# ArtixBank14.net
KiCad netlist of a schematic drawn in Altium Designer
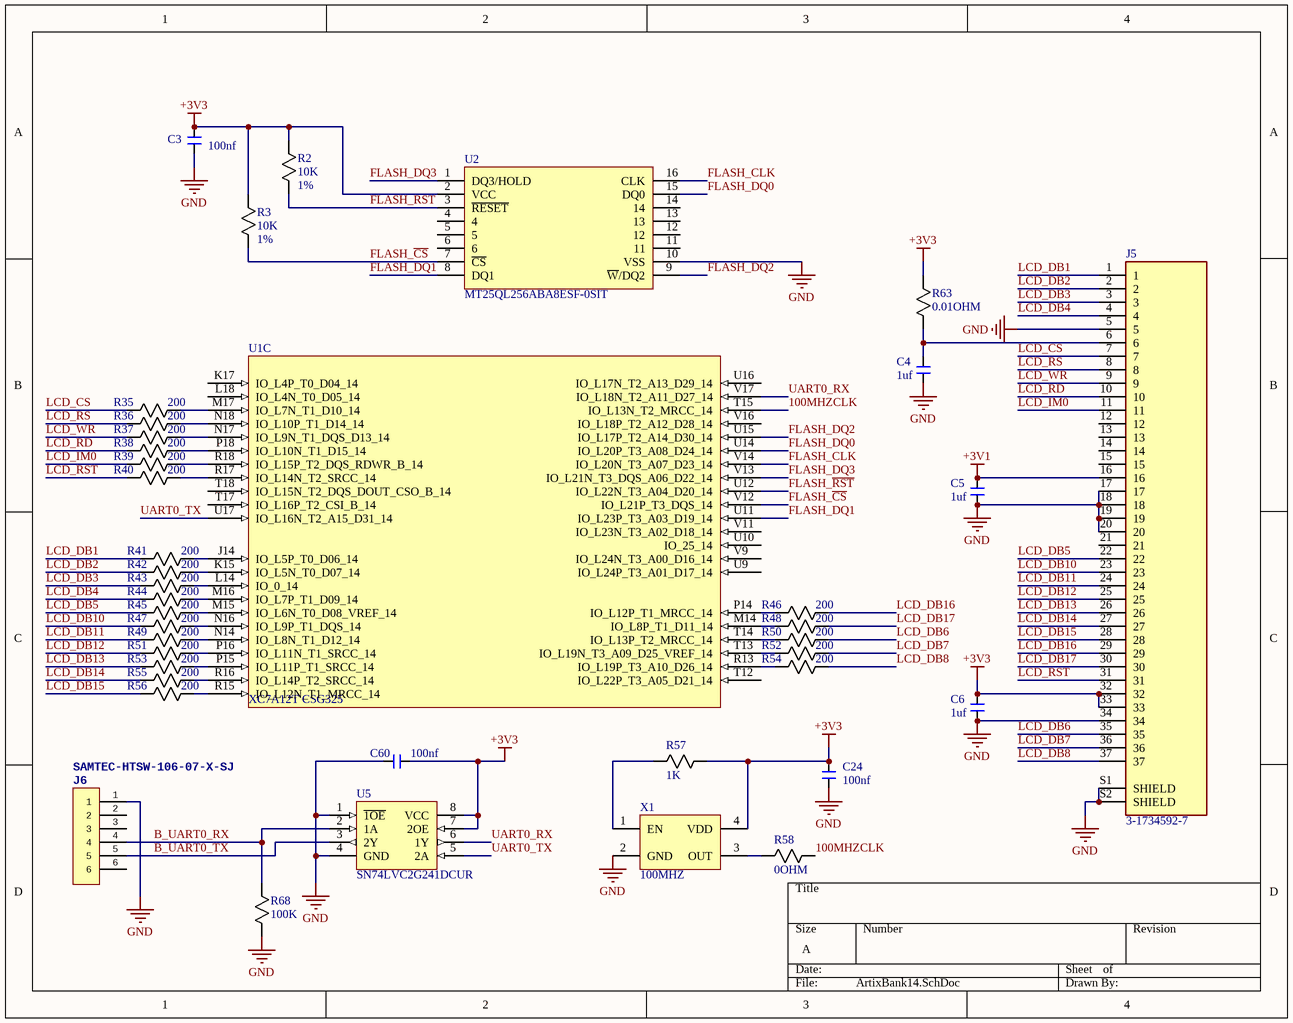
[diagram p0: ArtixBank14.SchDoc]

(export (version "E")
  (design (tool "Eeschema 10.0.6"))
  (components
    (comp (ref "C3")
      (value "100nf")
      (footprint "0402Footprint")
      (description "0402")
      (libsource (lib "Capacitors") (part "100nf_0402"))
    )
    (comp (ref "C4")
      (value "1uf")
      (footprint "0402Footprint")
      (description "0402")
      (libsource (lib "Capacitors") (part "1uf_0402"))
    )
    (comp (ref "C5")
      (value "1uf")
      (footprint "0402Footprint")
      (description "0402")
      (libsource (lib "Capacitors") (part "1uf_0402"))
    )
    (comp (ref "C6")
      (value "1uf")
      (footprint "0402Footprint")
      (description "0402")
      (libsource (lib "Capacitors") (part "1uf_0402"))
    )
    (comp (ref "C24")
      (value "100nf")
      (footprint "0402Footprint")
      (description "0402")
      (libsource (lib "Capacitors") (part "100nf_0402"))
    )
    (comp (ref "C60")
      (value "100nf")
      (footprint "0402Footprint")
      (description "0402")
      (libsource (lib "Capacitors") (part "100nf_0402"))
    )
    (comp (ref "J5")
      (value "3-1734592-7")
      (footprint "TE_3-1734592-7")
      (description "Conn FPC Connector SKT 37 POS 0.5mm Solder RA SMD T/R")
      (fields (field (name "MF") "TE Connectivity"))
      (libsource (lib "3-1734592-7") (part "3-1734592-7"))
    )
    (comp (ref "J6")
      (value "SAMTEC-HTSW-106-07-X-SJ")
      (footprint "SAMTEC-HTSW-106-07-X-S")
      (description "6 pin 2.54mm pitch header")
      (libsource (lib "Connectors") (part "SAMTEC-HTSW-106-07-X-SJ"))
    )
    (comp (ref "R2")
      (value "10K")
      (footprint "RES_CRCW_0402")
      (description "0402")
      (fields (field (name "TOLERANCE") "1%"))
      (libsource (lib "Resistors") (part "10K_0402"))
    )
    (comp (ref "R3")
      (value "10K")
      (footprint "RES_CRCW_0402")
      (description "0402")
      (fields (field (name "TOLERANCE") "1%"))
      (libsource (lib "Resistors") (part "10K_0402"))
    )
    (comp (ref "R35")
      (value "200")
      (footprint "RES_CRCW_0402")
      (description "0402")
      (fields (field (name "TOLERANCE") "1%"))
      (libsource (lib "Resistors") (part "200OHM_0402"))
    )
    (comp (ref "R36")
      (value "200")
      (footprint "RES_CRCW_0402")
      (description "0402")
      (fields (field (name "TOLERANCE") "1%"))
      (libsource (lib "Resistors") (part "200OHM_0402"))
    )
    (comp (ref "R37")
      (value "200")
      (footprint "RES_CRCW_0402")
      (description "0402")
      (fields (field (name "TOLERANCE") "1%"))
      (libsource (lib "Resistors") (part "200OHM_0402"))
    )
    (comp (ref "R38")
      (value "200")
      (footprint "RES_CRCW_0402")
      (description "0402")
      (fields (field (name "TOLERANCE") "1%"))
      (libsource (lib "Resistors") (part "200OHM_0402"))
    )
    (comp (ref "R39")
      (value "200")
      (footprint "RES_CRCW_0402")
      (description "0402")
      (fields (field (name "TOLERANCE") "1%"))
      (libsource (lib "Resistors") (part "200OHM_0402"))
    )
    (comp (ref "R40")
      (value "200")
      (footprint "RES_CRCW_0402")
      (description "0402")
      (fields (field (name "TOLERANCE") "1%"))
      (libsource (lib "Resistors") (part "200OHM_0402"))
    )
    (comp (ref "R41")
      (value "200")
      (footprint "RES_CRCW_0402")
      (description "0402")
      (fields (field (name "TOLERANCE") "1%"))
      (libsource (lib "Resistors") (part "200OHM_0402"))
    )
    (comp (ref "R42")
      (value "200")
      (footprint "RES_CRCW_0402")
      (description "0402")
      (fields (field (name "TOLERANCE") "1%"))
      (libsource (lib "Resistors") (part "200OHM_0402"))
    )
    (comp (ref "R43")
      (value "200")
      (footprint "RES_CRCW_0402")
      (description "0402")
      (fields (field (name "TOLERANCE") "1%"))
      (libsource (lib "Resistors") (part "200OHM_0402"))
    )
    (comp (ref "R44")
      (value "200")
      (footprint "RES_CRCW_0402")
      (description "0402")
      (fields (field (name "TOLERANCE") "1%"))
      (libsource (lib "Resistors") (part "200OHM_0402"))
    )
    (comp (ref "R45")
      (value "200")
      (footprint "RES_CRCW_0402")
      (description "0402")
      (fields (field (name "TOLERANCE") "1%"))
      (libsource (lib "Resistors") (part "200OHM_0402"))
    )
    (comp (ref "R46")
      (value "200")
      (footprint "RES_CRCW_0402")
      (description "0402")
      (fields (field (name "TOLERANCE") "1%"))
      (libsource (lib "Resistors") (part "200OHM_0402"))
    )
    (comp (ref "R47")
      (value "200")
      (footprint "RES_CRCW_0402")
      (description "0402")
      (fields (field (name "TOLERANCE") "1%"))
      (libsource (lib "Resistors") (part "200OHM_0402"))
    )
    (comp (ref "R48")
      (value "200")
      (footprint "RES_CRCW_0402")
      (description "0402")
      (fields (field (name "TOLERANCE") "1%"))
      (libsource (lib "Resistors") (part "200OHM_0402"))
    )
    (comp (ref "R49")
      (value "200")
      (footprint "RES_CRCW_0402")
      (description "0402")
      (fields (field (name "TOLERANCE") "1%"))
      (libsource (lib "Resistors") (part "200OHM_0402"))
    )
    (comp (ref "R50")
      (value "200")
      (footprint "RES_CRCW_0402")
      (description "0402")
      (fields (field (name "TOLERANCE") "1%"))
      (libsource (lib "Resistors") (part "200OHM_0402"))
    )
    (comp (ref "R51")
      (value "200")
      (footprint "RES_CRCW_0402")
      (description "0402")
      (fields (field (name "TOLERANCE") "1%"))
      (libsource (lib "Resistors") (part "200OHM_0402"))
    )
    (comp (ref "R52")
      (value "200")
      (footprint "RES_CRCW_0402")
      (description "0402")
      (fields (field (name "TOLERANCE") "1%"))
      (libsource (lib "Resistors") (part "200OHM_0402"))
    )
    (comp (ref "R53")
      (value "200")
      (footprint "RES_CRCW_0402")
      (description "0402")
      (fields (field (name "TOLERANCE") "1%"))
      (libsource (lib "Resistors") (part "200OHM_0402"))
    )
    (comp (ref "R54")
      (value "200")
      (footprint "RES_CRCW_0402")
      (description "0402")
      (fields (field (name "TOLERANCE") "1%"))
      (libsource (lib "Resistors") (part "200OHM_0402"))
    )
    (comp (ref "R55")
      (value "200")
      (footprint "RES_CRCW_0402")
      (description "0402")
      (fields (field (name "TOLERANCE") "1%"))
      (libsource (lib "Resistors") (part "200OHM_0402"))
    )
    (comp (ref "R56")
      (value "200")
      (footprint "RES_CRCW_0402")
      (description "0402")
      (fields (field (name "TOLERANCE") "1%"))
      (libsource (lib "Resistors") (part "200OHM_0402"))
    )
    (comp (ref "R57")
      (value "1K")
      (footprint "RES_CRCW_0402")
      (description "0402")
      (fields (field (name "TOLERANCE") "1%"))
      (libsource (lib "Resistors") (part "1k_0402"))
    )
    (comp (ref "R58")
      (value "0OHM")
      (footprint "RES_CRCW_0402")
      (description "0402")
      (libsource (lib "Resistors") (part "0OHM_0402"))
    )
    (comp (ref "R63")
      (value "0.01OHM")
      (footprint "RESC1508X06N")
      (description "0603")
      (libsource (lib "Resistors") (part "0.01OHM_0603"))
    )
    (comp (ref "R68")
      (value "100K")
      (footprint "RES_CRCW_0402")
      (description "0402")
      (fields (field (name "TOLERANCE") "1%"))
      (libsource (lib "Resistors") (part "100K_0402"))
    )
    (comp (ref "U1")
      (value "XC7A12T CSG325")
      (footprint "BGA324C80P18X18_1500X1500X150")
      (libsource (lib "XC7A12T_1CPG238I") (part "XC7A12T_1CSG325I"))
    )
    (comp (ref "U2")
      (value "MT25QL256ABA8ESF-0SIT")
      (footprint "SOP127P1030X265-16N")
      (description "256 Mb Flash Micron")
      (libsource (lib "MT25QL256ABA") (part "MT25QL256ABA8ESF-0SIT"))
    )
    (comp (ref "U5")
      (value "SN74LVC2G241DCUR")
      (footprint "SOP50P310X90-8N")
      (description "Buffer, Non-Inverting 2 Element 1 Bit per Element 3-State Output 8-VSSOP")
      (fields (field (name "MF") "Texas Instruments"))
      (libsource (lib "SN74LVC2G241DCUR") (part "SN74LVC2G241DCUR"))
    )
    (comp (ref "X1")
      (value "100MHZ")
      (footprint "SIT8008AI-12-33E-100.000000E")
      (libsource (lib "Oscillators") (part "SIT8008AI-12-33E-100.000000E"))
    )
  )
  (nets
    (net (code "1") (name "+3V1") (class "Default")
      (node (ref "C5") (pin "1") (pinfunction "1_1") (pintype "passive"))
      (node (ref "J5") (pin "16") (pinfunction "16_16") (pintype "passive"))
    )
    (net (code "2") (name "+3V3") (class "Default")
      (node (ref "C24") (pin "1") (pinfunction "1_1") (pintype "passive"))
      (node (ref "C3") (pin "1") (pinfunction "1_1") (pintype "passive"))
      (node (ref "C6") (pin "1") (pinfunction "1_1") (pintype "passive"))
      (node (ref "C60") (pin "1") (pinfunction "1_1") (pintype "passive"))
      (node (ref "J5") (pin "32") (pinfunction "32_32") (pintype "passive"))
      (node (ref "J5") (pin "33") (pinfunction "33_33") (pintype "passive"))
      (node (ref "R2") (pin "1") (pinfunction "1_1") (pintype "passive"))
      (node (ref "R3") (pin "1") (pinfunction "1_1") (pintype "passive"))
      (node (ref "R57") (pin "1") (pinfunction "1_1") (pintype "passive"))
      (node (ref "R63") (pin "1") (pinfunction "1_1") (pintype "passive"))
      (node (ref "U2") (pin "2") (pinfunction "VCC_2") (pintype "passive"))
      (node (ref "U5") (pin "7") (pinfunction "2OE_7") (pintype "input"))
      (node (ref "U5") (pin "8") (pinfunction "VCC_8") (pintype "power_in"))
      (node (ref "X1") (pin "4") (pinfunction "VDD_4") (pintype "passive"))
    )
    (net (code "3") (name "/100MHZCLK") (class "Default")
      (node (ref "R58") (pin "1") (pinfunction "1_1") (pintype "passive"))
      (node (ref "U1") (pin "T15") (pinfunction "IO_L13N_T2_MRCC_14_T15") (pintype "input"))
    )
    (net (code "4") (name "/B_UART0_RX") (class "Default")
      (node (ref "J6") (pin "4") (pinfunction "4_4") (pintype "passive"))
      (node (ref "R68") (pin "1") (pinfunction "1_1") (pintype "passive"))
      (node (ref "U5") (pin "2") (pinfunction "1A_2") (pintype "input"))
    )
    (net (code "5") (name "/B_UART0_TX") (class "Default")
      (node (ref "J6") (pin "5") (pinfunction "5_5") (pintype "passive"))
      (node (ref "U5") (pin "3") (pinfunction "2Y_3") (pintype "output"))
    )
    (net (code "6") (name "/FLASH_CLK") (class "Default")
      (node (ref "U1") (pin "V14") (pinfunction "IO_L20N_T3_A07_D23_14_V14") (pintype "input"))
      (node (ref "U2") (pin "16") (pinfunction "CLK_16") (pintype "passive"))
    )
    (net (code "7") (name "/FLASH_DQ0") (class "Default")
      (node (ref "U1") (pin "U14") (pinfunction "IO_L20P_T3_A08_D24_14_U14") (pintype "input"))
      (node (ref "U2") (pin "15") (pinfunction "DQ0_15") (pintype "passive"))
    )
    (net (code "8") (name "/FLASH_DQ1") (class "Default")
      (node (ref "U1") (pin "U11") (pinfunction "IO_L23P_T3_A03_D19_14_U11") (pintype "input"))
      (node (ref "U2") (pin "8") (pinfunction "DQ1_8") (pintype "passive"))
    )
    (net (code "9") (name "/FLASH_DQ2") (class "Default")
      (node (ref "U1") (pin "U15") (pinfunction "IO_L17P_T2_A14_D30_14_U15") (pintype "input"))
      (node (ref "U2") (pin "9") (pinfunction "~{W}/DQ2_9") (pintype "passive"))
    )
    (net (code "10") (name "/FLASH_DQ3") (class "Default")
      (node (ref "U1") (pin "V13") (pinfunction "IO_L21N_T3_DQS_A06_D22_14_V13") (pintype "input"))
      (node (ref "U2") (pin "1") (pinfunction "DQ3/HOLD_1") (pintype "passive"))
    )
    (net (code "11") (name "/FLASH_~{CS}") (class "Default")
      (node (ref "R3") (pin "2") (pinfunction "2_2") (pintype "passive"))
      (node (ref "U1") (pin "V12") (pinfunction "IO_L21P_T3_DQS_14_V12") (pintype "input"))
      (node (ref "U2") (pin "7") (pinfunction "~{CS}_7") (pintype "passive"))
    )
    (net (code "12") (name "/FLASH_~{RST}") (class "Default")
      (node (ref "R2") (pin "2") (pinfunction "2_2") (pintype "passive"))
      (node (ref "U1") (pin "U12") (pinfunction "IO_L22N_T3_A04_D20_14_U12") (pintype "input"))
      (node (ref "U2") (pin "3") (pinfunction "~{RESET}_3") (pintype "passive"))
    )
    (net (code "13") (name "/LCD_CS") (class "Default")
      (node (ref "J5") (pin "7") (pinfunction "7_7") (pintype "passive"))
      (node (ref "R35") (pin "2") (pinfunction "2_2") (pintype "passive"))
    )
    (net (code "14") (name "/LCD_DB1") (class "Default")
      (node (ref "J5") (pin "1") (pinfunction "1_1") (pintype "passive"))
      (node (ref "R41") (pin "2") (pinfunction "2_2") (pintype "passive"))
    )
    (net (code "15") (name "/LCD_DB2") (class "Default")
      (node (ref "J5") (pin "2") (pinfunction "2_2") (pintype "passive"))
      (node (ref "R42") (pin "2") (pinfunction "2_2") (pintype "passive"))
    )
    (net (code "16") (name "/LCD_DB3") (class "Default")
      (node (ref "J5") (pin "3") (pinfunction "3_3") (pintype "passive"))
      (node (ref "R43") (pin "2") (pinfunction "2_2") (pintype "passive"))
    )
    (net (code "17") (name "/LCD_DB4") (class "Default")
      (node (ref "J5") (pin "4") (pinfunction "4_4") (pintype "passive"))
      (node (ref "R44") (pin "2") (pinfunction "2_2") (pintype "passive"))
    )
    (net (code "18") (name "/LCD_DB5") (class "Default")
      (node (ref "J5") (pin "22") (pinfunction "22_22") (pintype "passive"))
      (node (ref "R45") (pin "2") (pinfunction "2_2") (pintype "passive"))
    )
    (net (code "19") (name "/LCD_DB6") (class "Default")
      (node (ref "J5") (pin "35") (pinfunction "35_35") (pintype "passive"))
      (node (ref "R50") (pin "1") (pinfunction "1_1") (pintype "passive"))
    )
    (net (code "20") (name "/LCD_DB7") (class "Default")
      (node (ref "J5") (pin "36") (pinfunction "36_36") (pintype "passive"))
      (node (ref "R52") (pin "1") (pinfunction "1_1") (pintype "passive"))
    )
    (net (code "21") (name "/LCD_DB8") (class "Default")
      (node (ref "J5") (pin "37") (pinfunction "37_37") (pintype "passive"))
      (node (ref "R54") (pin "1") (pinfunction "1_1") (pintype "passive"))
    )
    (net (code "22") (name "/LCD_DB10") (class "Default")
      (node (ref "J5") (pin "23") (pinfunction "23_23") (pintype "passive"))
      (node (ref "R47") (pin "2") (pinfunction "2_2") (pintype "passive"))
    )
    (net (code "23") (name "/LCD_DB11") (class "Default")
      (node (ref "J5") (pin "24") (pinfunction "24_24") (pintype "passive"))
      (node (ref "R49") (pin "2") (pinfunction "2_2") (pintype "passive"))
    )
    (net (code "24") (name "/LCD_DB12") (class "Default")
      (node (ref "J5") (pin "25") (pinfunction "25_25") (pintype "passive"))
      (node (ref "R51") (pin "2") (pinfunction "2_2") (pintype "passive"))
    )
    (net (code "25") (name "/LCD_DB13") (class "Default")
      (node (ref "J5") (pin "26") (pinfunction "26_26") (pintype "passive"))
      (node (ref "R53") (pin "2") (pinfunction "2_2") (pintype "passive"))
    )
    (net (code "26") (name "/LCD_DB14") (class "Default")
      (node (ref "J5") (pin "27") (pinfunction "27_27") (pintype "passive"))
      (node (ref "R55") (pin "2") (pinfunction "2_2") (pintype "passive"))
    )
    (net (code "27") (name "/LCD_DB15") (class "Default")
      (node (ref "J5") (pin "28") (pinfunction "28_28") (pintype "passive"))
      (node (ref "R56") (pin "2") (pinfunction "2_2") (pintype "passive"))
    )
    (net (code "28") (name "/LCD_DB16") (class "Default")
      (node (ref "J5") (pin "29") (pinfunction "29_29") (pintype "passive"))
      (node (ref "R46") (pin "1") (pinfunction "1_1") (pintype "passive"))
    )
    (net (code "29") (name "/LCD_DB17") (class "Default")
      (node (ref "J5") (pin "30") (pinfunction "30_30") (pintype "passive"))
      (node (ref "R48") (pin "1") (pinfunction "1_1") (pintype "passive"))
    )
    (net (code "30") (name "/LCD_IM0") (class "Default")
      (node (ref "J5") (pin "11") (pinfunction "11_11") (pintype "passive"))
      (node (ref "R39") (pin "2") (pinfunction "2_2") (pintype "passive"))
    )
    (net (code "31") (name "/LCD_RD") (class "Default")
      (node (ref "J5") (pin "10") (pinfunction "10_10") (pintype "passive"))
      (node (ref "R38") (pin "2") (pinfunction "2_2") (pintype "passive"))
    )
    (net (code "32") (name "/LCD_RS") (class "Default")
      (node (ref "J5") (pin "8") (pinfunction "8_8") (pintype "passive"))
      (node (ref "R36") (pin "2") (pinfunction "2_2") (pintype "passive"))
    )
    (net (code "33") (name "/LCD_RST") (class "Default")
      (node (ref "J5") (pin "31") (pinfunction "31_31") (pintype "passive"))
      (node (ref "R40") (pin "2") (pinfunction "2_2") (pintype "passive"))
    )
    (net (code "34") (name "/LCD_WR") (class "Default")
      (node (ref "J5") (pin "9") (pinfunction "9_9") (pintype "passive"))
      (node (ref "R37") (pin "2") (pinfunction "2_2") (pintype "passive"))
    )
    (net (code "35") (name "/UART0_RX") (class "Default")
      (node (ref "U1") (pin "V17") (pinfunction "IO_L18N_T2_A11_D27_14_V17") (pintype "input"))
      (node (ref "U5") (pin "6") (pinfunction "1Y_6") (pintype "output"))
    )
    (net (code "36") (name "/UART0_TX") (class "Default")
      (node (ref "U1") (pin "U17") (pinfunction "IO_L16N_T2_A15_D31_14_U17") (pintype "input"))
      (node (ref "U5") (pin "5") (pinfunction "2A_5") (pintype "input"))
    )
    (net (code "37") (name "GND") (class "Default")
      (node (ref "C24") (pin "2") (pinfunction "2_2") (pintype "passive"))
      (node (ref "C3") (pin "2") (pinfunction "2_2") (pintype "passive"))
      (node (ref "C4") (pin "2") (pinfunction "2_2") (pintype "passive"))
      (node (ref "C5") (pin "2") (pinfunction "2_2") (pintype "passive"))
      (node (ref "C6") (pin "2") (pinfunction "2_2") (pintype "passive"))
      (node (ref "C60") (pin "2") (pinfunction "2_2") (pintype "passive"))
      (node (ref "J5") (pin "17") (pinfunction "17_17") (pintype "passive"))
      (node (ref "J5") (pin "18") (pinfunction "18_18") (pintype "passive"))
      (node (ref "J5") (pin "19") (pinfunction "19_19") (pintype "passive"))
      (node (ref "J5") (pin "20") (pinfunction "20_20") (pintype "passive"))
      (node (ref "J5") (pin "34") (pinfunction "34_34") (pintype "passive"))
      (node (ref "J5") (pin "5") (pinfunction "5_5") (pintype "passive"))
      (node (ref "J5") (pin "S1") (pinfunction "SHIELD_S1") (pintype "passive"))
      (node (ref "J5") (pin "S2") (pinfunction "SHIELD_S2") (pintype "passive"))
      (node (ref "J6") (pin "1") (pinfunction "1_1") (pintype "passive"))
      (node (ref "R68") (pin "2") (pinfunction "2_2") (pintype "passive"))
      (node (ref "U2") (pin "10") (pinfunction "VSS_10") (pintype "passive"))
      (node (ref "U5") (pin "1") (pinfunction "~{1OE}_1") (pintype "input"))
      (node (ref "U5") (pin "4") (pinfunction "GND_4") (pintype "passive"))
      (node (ref "X1") (pin "2") (pinfunction "GND_2") (pintype "passive"))
    )
    (net (code "38") (name "Net-(C4-Pad1)") (class "Default")
      (node (ref "C4") (pin "1") (pinfunction "1_1") (pintype "passive"))
      (node (ref "J5") (pin "6") (pinfunction "6_6") (pintype "passive"))
      (node (ref "R63") (pin "2") (pinfunction "2_2") (pintype "passive"))
    )
    (net (code "39") (name "Net-(U1C-IO_0_14)") (class "Default")
      (node (ref "R43") (pin "1") (pinfunction "1_1") (pintype "passive"))
      (node (ref "U1") (pin "L14") (pinfunction "IO_0_14_L14") (pintype "input"))
    )
    (net (code "40") (name "Net-(U1C-IO_L5N_T0_D07_14)") (class "Default")
      (node (ref "R42") (pin "1") (pinfunction "1_1") (pintype "passive"))
      (node (ref "U1") (pin "K15") (pinfunction "IO_L5N_T0_D07_14_K15") (pintype "input"))
    )
    (net (code "41") (name "Net-(U1C-IO_L5P_T0_D06_14)") (class "Default")
      (node (ref "R41") (pin "1") (pinfunction "1_1") (pintype "passive"))
      (node (ref "U1") (pin "J14") (pinfunction "IO_L5P_T0_D06_14_J14") (pintype "input"))
    )
    (net (code "42") (name "Net-(U1C-IO_L6N_T0_D08_VREF_14)") (class "Default")
      (node (ref "R45") (pin "1") (pinfunction "1_1") (pintype "passive"))
      (node (ref "U1") (pin "M15") (pinfunction "IO_L6N_T0_D08_VREF_14_M15") (pintype "input"))
    )
    (net (code "43") (name "Net-(U1C-IO_L7N_T1_D10_14)") (class "Default")
      (node (ref "R35") (pin "1") (pinfunction "1_1") (pintype "passive"))
      (node (ref "U1") (pin "M17") (pinfunction "IO_L7N_T1_D10_14_M17") (pintype "input"))
    )
    (net (code "44") (name "Net-(U1C-IO_L7P_T1_D09_14)") (class "Default")
      (node (ref "R44") (pin "1") (pinfunction "1_1") (pintype "passive"))
      (node (ref "U1") (pin "M16") (pinfunction "IO_L7P_T1_D09_14_M16") (pintype "input"))
    )
    (net (code "45") (name "Net-(U1C-IO_L8N_T1_D12_14)") (class "Default")
      (node (ref "R49") (pin "1") (pinfunction "1_1") (pintype "passive"))
      (node (ref "U1") (pin "N14") (pinfunction "IO_L8N_T1_D12_14_N14") (pintype "input"))
    )
    (net (code "46") (name "Net-(U1C-IO_L8P_T1_D11_14)") (class "Default")
      (node (ref "R48") (pin "2") (pinfunction "2_2") (pintype "passive"))
      (node (ref "U1") (pin "M14") (pinfunction "IO_L8P_T1_D11_14_M14") (pintype "input"))
    )
    (net (code "47") (name "Net-(U1C-IO_L9N_T1_DQS_D13_14)") (class "Default")
      (node (ref "R37") (pin "1") (pinfunction "1_1") (pintype "passive"))
      (node (ref "U1") (pin "N17") (pinfunction "IO_L9N_T1_DQS_D13_14_N17") (pintype "input"))
    )
    (net (code "48") (name "Net-(U1C-IO_L9P_T1_DQS_14)") (class "Default")
      (node (ref "R47") (pin "1") (pinfunction "1_1") (pintype "passive"))
      (node (ref "U1") (pin "N16") (pinfunction "IO_L9P_T1_DQS_14_N16") (pintype "input"))
    )
    (net (code "49") (name "Net-(U1C-IO_L10N_T1_D15_14)") (class "Default")
      (node (ref "R38") (pin "1") (pinfunction "1_1") (pintype "passive"))
      (node (ref "U1") (pin "P18") (pinfunction "IO_L10N_T1_D15_14_P18") (pintype "input"))
    )
    (net (code "50") (name "Net-(U1C-IO_L10P_T1_D14_14)") (class "Default")
      (node (ref "R36") (pin "1") (pinfunction "1_1") (pintype "passive"))
      (node (ref "U1") (pin "N18") (pinfunction "IO_L10P_T1_D14_14_N18") (pintype "input"))
    )
    (net (code "51") (name "Net-(U1C-IO_L11N_T1_SRCC_14)") (class "Default")
      (node (ref "R51") (pin "1") (pinfunction "1_1") (pintype "passive"))
      (node (ref "U1") (pin "P16") (pinfunction "IO_L11N_T1_SRCC_14_P16") (pintype "input"))
    )
    (net (code "52") (name "Net-(U1C-IO_L11P_T1_SRCC_14)") (class "Default")
      (node (ref "R53") (pin "1") (pinfunction "1_1") (pintype "passive"))
      (node (ref "U1") (pin "P15") (pinfunction "IO_L11P_T1_SRCC_14_P15") (pintype "input"))
    )
    (net (code "53") (name "Net-(U1C-IO_L12N_T1_MRCC_14)") (class "Default")
      (node (ref "R56") (pin "1") (pinfunction "1_1") (pintype "passive"))
      (node (ref "U1") (pin "R15") (pinfunction "IO_L12N_T1_MRCC_14_R15") (pintype "input"))
    )
    (net (code "54") (name "Net-(U1C-IO_L12P_T1_MRCC_14)") (class "Default")
      (node (ref "R46") (pin "2") (pinfunction "2_2") (pintype "passive"))
      (node (ref "U1") (pin "P14") (pinfunction "IO_L12P_T1_MRCC_14_P14") (pintype "input"))
    )
    (net (code "55") (name "Net-(U1C-IO_L13P_T2_MRCC_14)") (class "Default")
      (node (ref "R50") (pin "2") (pinfunction "2_2") (pintype "passive"))
      (node (ref "U1") (pin "T14") (pinfunction "IO_L13P_T2_MRCC_14_T14") (pintype "input"))
    )
    (net (code "56") (name "Net-(U1C-IO_L14N_T2_SRCC_14)") (class "Default")
      (node (ref "R40") (pin "1") (pinfunction "1_1") (pintype "passive"))
      (node (ref "U1") (pin "R17") (pinfunction "IO_L14N_T2_SRCC_14_R17") (pintype "input"))
    )
    (net (code "57") (name "Net-(U1C-IO_L14P_T2_SRCC_14)") (class "Default")
      (node (ref "R55") (pin "1") (pinfunction "1_1") (pintype "passive"))
      (node (ref "U1") (pin "R16") (pinfunction "IO_L14P_T2_SRCC_14_R16") (pintype "input"))
    )
    (net (code "58") (name "Net-(U1C-IO_L15P_T2_DQS_RDWR_B_14)") (class "Default")
      (node (ref "R39") (pin "1") (pinfunction "1_1") (pintype "passive"))
      (node (ref "U1") (pin "R18") (pinfunction "IO_L15P_T2_DQS_RDWR_B_14_R18") (pintype "input"))
    )
    (net (code "59") (name "Net-(U1C-IO_L19N_T3_A09_D25_VREF_14)") (class "Default")
      (node (ref "R52") (pin "2") (pinfunction "2_2") (pintype "passive"))
      (node (ref "U1") (pin "T13") (pinfunction "IO_L19N_T3_A09_D25_VREF_14_T13") (pintype "input"))
    )
    (net (code "60") (name "Net-(U1C-IO_L19P_T3_A10_D26_14)") (class "Default")
      (node (ref "R54") (pin "2") (pinfunction "2_2") (pintype "passive"))
      (node (ref "U1") (pin "R13") (pinfunction "IO_L19P_T3_A10_D26_14_R13") (pintype "input"))
    )
    (net (code "61") (name "Net-(X1-EN)") (class "Default")
      (node (ref "R57") (pin "2") (pinfunction "2_2") (pintype "passive"))
      (node (ref "X1") (pin "1") (pinfunction "EN_1") (pintype "passive"))
    )
    (net (code "62") (name "Net-(X1-OUT)") (class "Default")
      (node (ref "R58") (pin "2") (pinfunction "2_2") (pintype "passive"))
      (node (ref "X1") (pin "3") (pinfunction "OUT_3") (pintype "passive"))
    )
    (net (code "63") (name "unconnected-(J5-Pad12)") (class "Default")
      (node (ref "J5") (pin "12") (pinfunction "12_12") (pintype "passive"))
    )
    (net (code "64") (name "unconnected-(J5-Pad13)") (class "Default")
      (node (ref "J5") (pin "13") (pinfunction "13_13") (pintype "passive"))
    )
    (net (code "65") (name "unconnected-(J5-Pad14)") (class "Default")
      (node (ref "J5") (pin "14") (pinfunction "14_14") (pintype "passive"))
    )
    (net (code "66") (name "unconnected-(J5-Pad15)") (class "Default")
      (node (ref "J5") (pin "15") (pinfunction "15_15") (pintype "passive"))
    )
    (net (code "67") (name "unconnected-(J5-Pad21)") (class "Default")
      (node (ref "J5") (pin "21") (pinfunction "21_21") (pintype "passive"))
    )
    (net (code "68") (name "unconnected-(J6-Pad2)") (class "Default")
      (node (ref "J6") (pin "2") (pinfunction "2_2") (pintype "passive"))
    )
    (net (code "69") (name "unconnected-(J6-Pad3)") (class "Default")
      (node (ref "J6") (pin "3") (pinfunction "3_3") (pintype "passive"))
    )
    (net (code "70") (name "unconnected-(J6-Pad6)") (class "Default")
      (node (ref "J6") (pin "6") (pinfunction "6_6") (pintype "passive"))
    )
    (net (code "71") (name "unconnected-(U1C-IO_25_14-PadU10)") (class "Default")
      (node (ref "U1") (pin "U10") (pinfunction "IO_25_14_U10") (pintype "input"))
    )
    (net (code "72") (name "unconnected-(U1C-IO_L4N_T0_D05_14-PadL18)") (class "Default")
      (node (ref "U1") (pin "L18") (pinfunction "IO_L4N_T0_D05_14_L18") (pintype "input"))
    )
    (net (code "73") (name "unconnected-(U1C-IO_L4P_T0_D04_14-PadK17)") (class "Default")
      (node (ref "U1") (pin "K17") (pinfunction "IO_L4P_T0_D04_14_K17") (pintype "input"))
    )
    (net (code "74") (name "unconnected-(U1C-IO_L15N_T2_DQS_DOUT_CSO_B_14-PadT18)") (class "Default")
      (node (ref "U1") (pin "T18") (pinfunction "IO_L15N_T2_DQS_DOUT_CSO_B_14_T18") (pintype "input"))
    )
    (net (code "75") (name "unconnected-(U1C-IO_L16P_T2_CSI_B_14-PadT17)") (class "Default")
      (node (ref "U1") (pin "T17") (pinfunction "IO_L16P_T2_CSI_B_14_T17") (pintype "input"))
    )
    (net (code "76") (name "unconnected-(U1C-IO_L17N_T2_A13_D29_14-PadU16)") (class "Default")
      (node (ref "U1") (pin "U16") (pinfunction "IO_L17N_T2_A13_D29_14_U16") (pintype "input"))
    )
    (net (code "77") (name "unconnected-(U1C-IO_L18P_T2_A12_D28_14-PadV16)") (class "Default")
      (node (ref "U1") (pin "V16") (pinfunction "IO_L18P_T2_A12_D28_14_V16") (pintype "input"))
    )
    (net (code "78") (name "unconnected-(U1C-IO_L22P_T3_A05_D21_14-PadT12)") (class "Default")
      (node (ref "U1") (pin "T12") (pinfunction "IO_L22P_T3_A05_D21_14_T12") (pintype "input"))
    )
    (net (code "79") (name "unconnected-(U1C-IO_L23N_T3_A02_D18_14-PadV11)") (class "Default")
      (node (ref "U1") (pin "V11") (pinfunction "IO_L23N_T3_A02_D18_14_V11") (pintype "input"))
    )
    (net (code "80") (name "unconnected-(U1C-IO_L24N_T3_A00_D16_14-PadV9)") (class "Default")
      (node (ref "U1") (pin "V9") (pinfunction "IO_L24N_T3_A00_D16_14_V9") (pintype "input"))
    )
    (net (code "81") (name "unconnected-(U1C-IO_L24P_T3_A01_D17_14-PadU9)") (class "Default")
      (node (ref "U1") (pin "U9") (pinfunction "IO_L24P_T3_A01_D17_14_U9") (pintype "input"))
    )
    (net (code "82") (name "unconnected-(U2-Pad4)") (class "Default")
      (node (ref "U2") (pin "4") (pinfunction "4_4") (pintype "passive"))
    )
    (net (code "83") (name "unconnected-(U2-Pad5)") (class "Default")
      (node (ref "U2") (pin "5") (pinfunction "5_5") (pintype "passive"))
    )
    (net (code "84") (name "unconnected-(U2-Pad6)") (class "Default")
      (node (ref "U2") (pin "6") (pinfunction "6_6") (pintype "passive"))
    )
    (net (code "85") (name "unconnected-(U2-Pad11)") (class "Default")
      (node (ref "U2") (pin "11") (pinfunction "11_11") (pintype "passive"))
    )
    (net (code "86") (name "unconnected-(U2-Pad12)") (class "Default")
      (node (ref "U2") (pin "12") (pinfunction "12_12") (pintype "passive"))
    )
    (net (code "87") (name "unconnected-(U2-Pad13)") (class "Default")
      (node (ref "U2") (pin "13") (pinfunction "13_13") (pintype "passive"))
    )
    (net (code "88") (name "unconnected-(U2-Pad14)") (class "Default")
      (node (ref "U2") (pin "14") (pinfunction "14_14") (pintype "passive"))
    )
  )
)
